# Decoder4_2.net
KiCad netlist of a schematic drawn in EAGLE
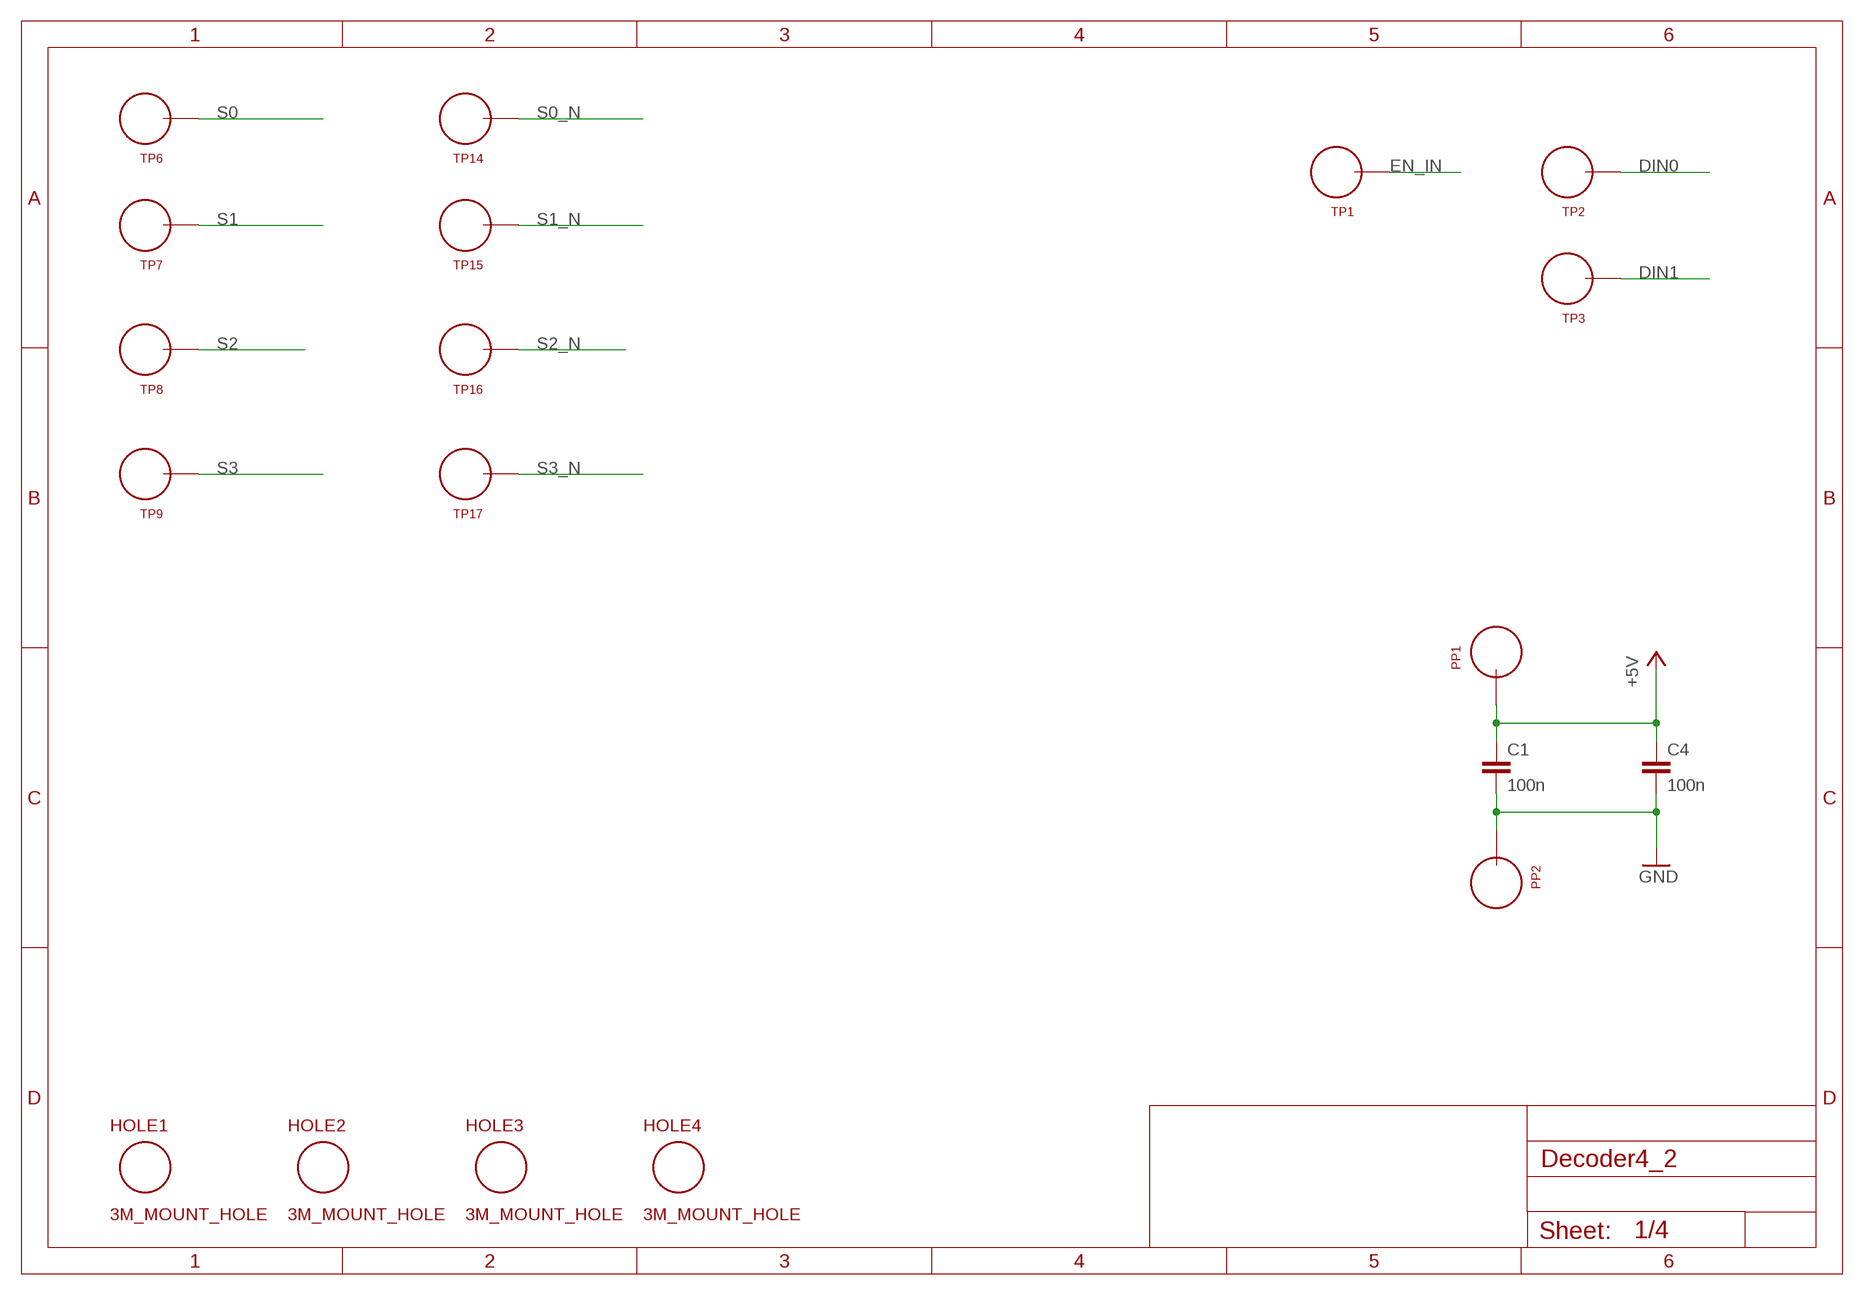
[diagram p0: schematic, sheet 1]
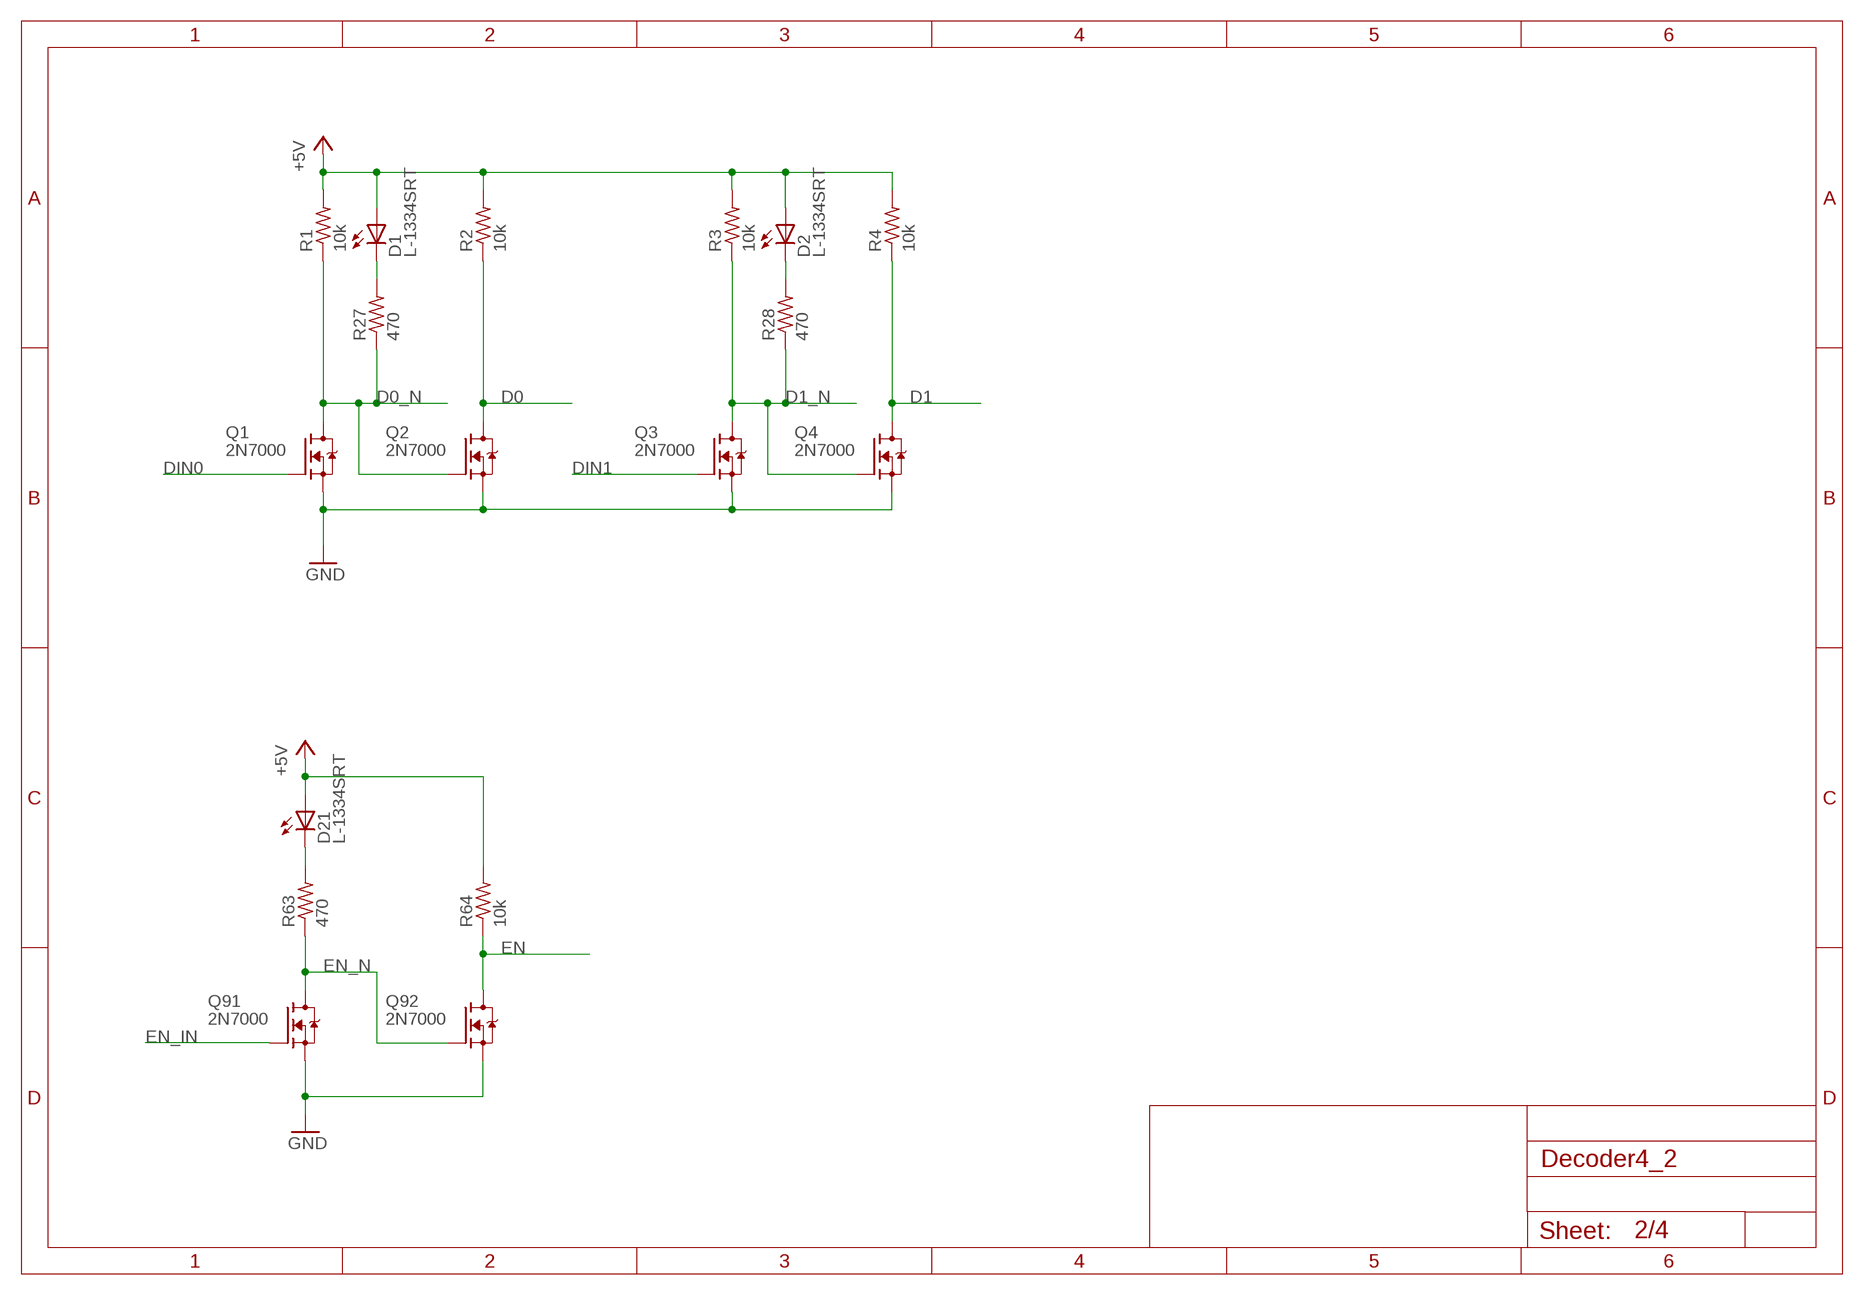
[diagram p1: schematic, sheet 2]
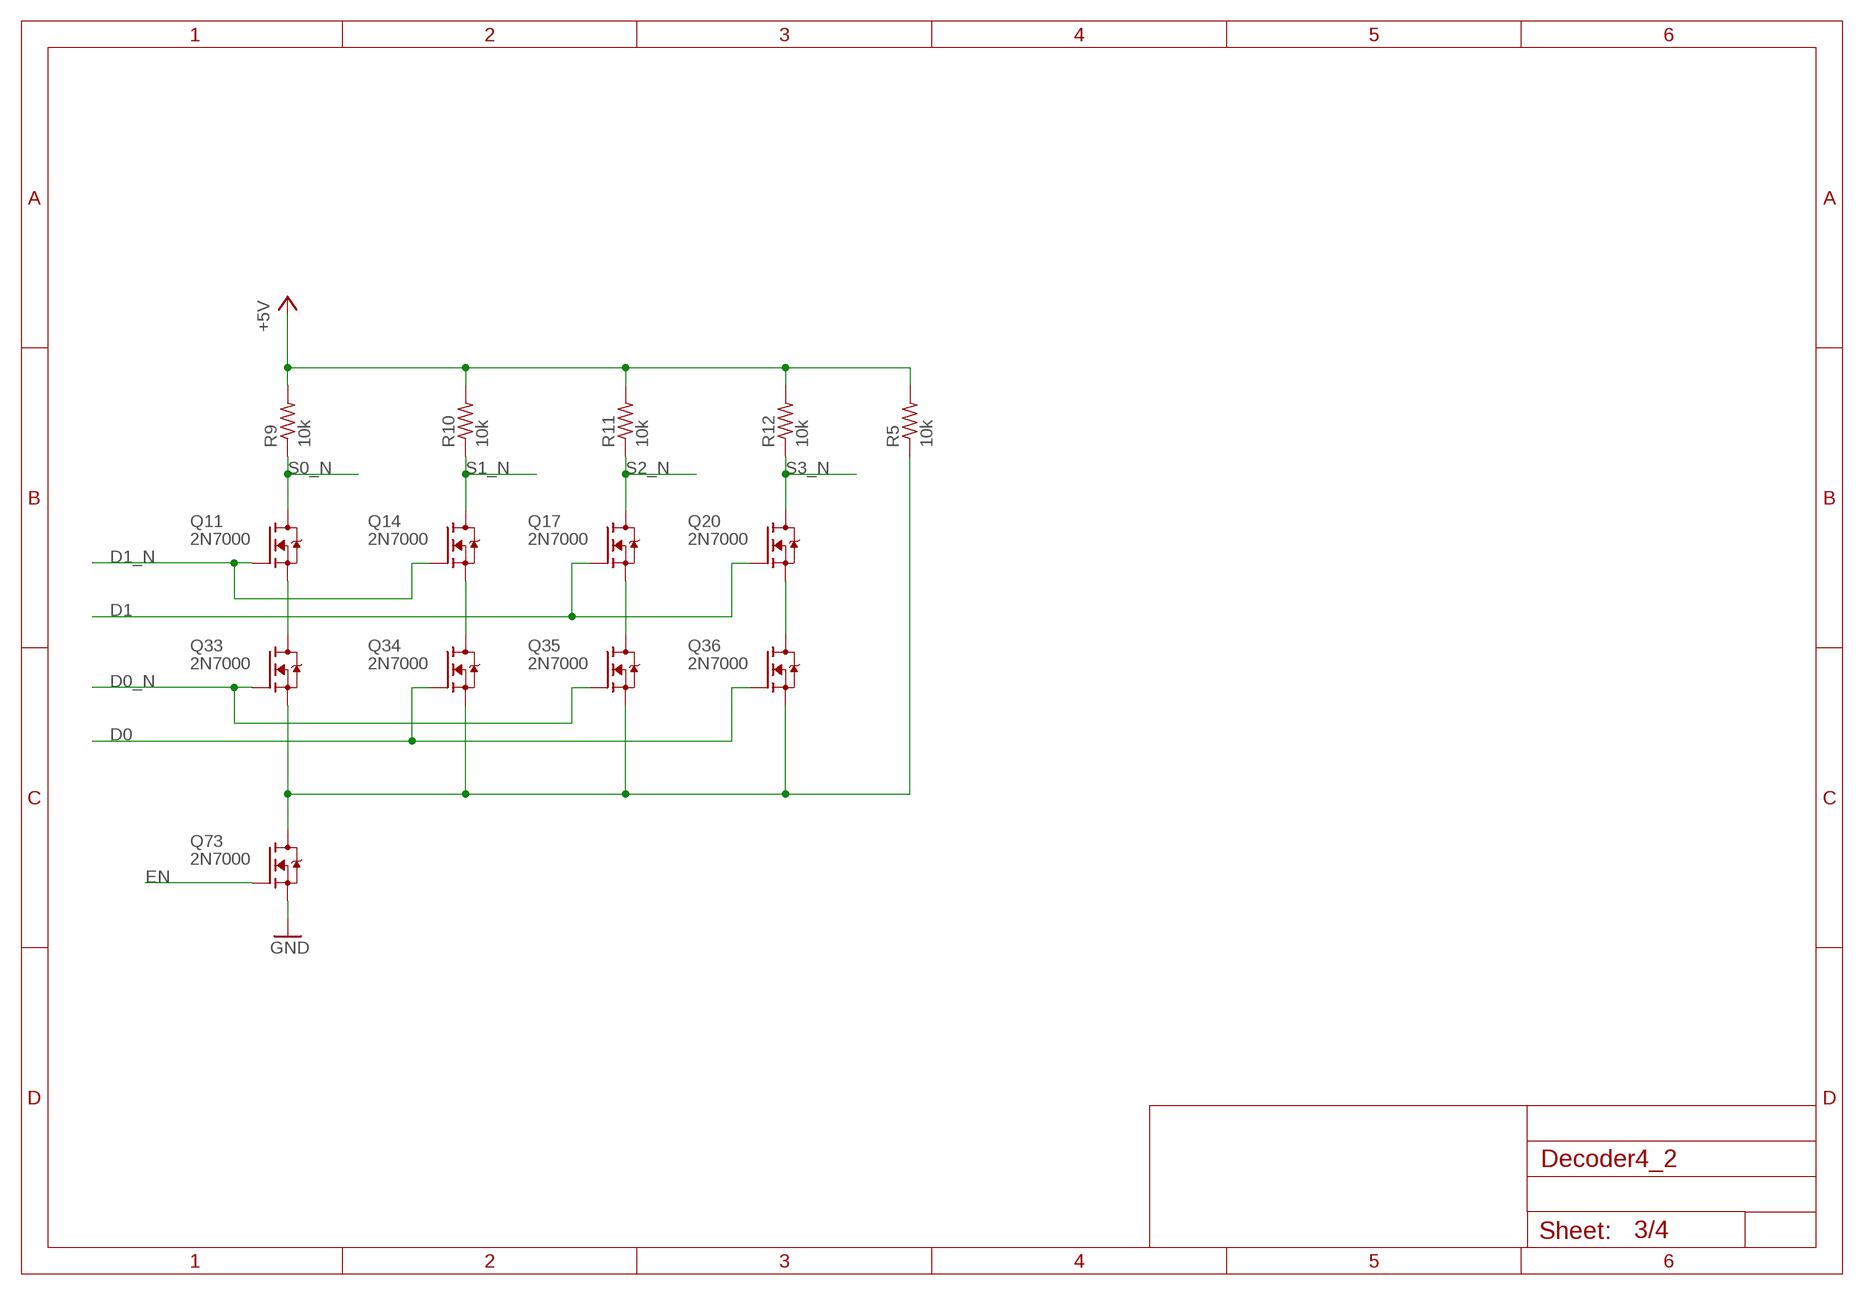
[diagram p2: schematic, sheet 3]
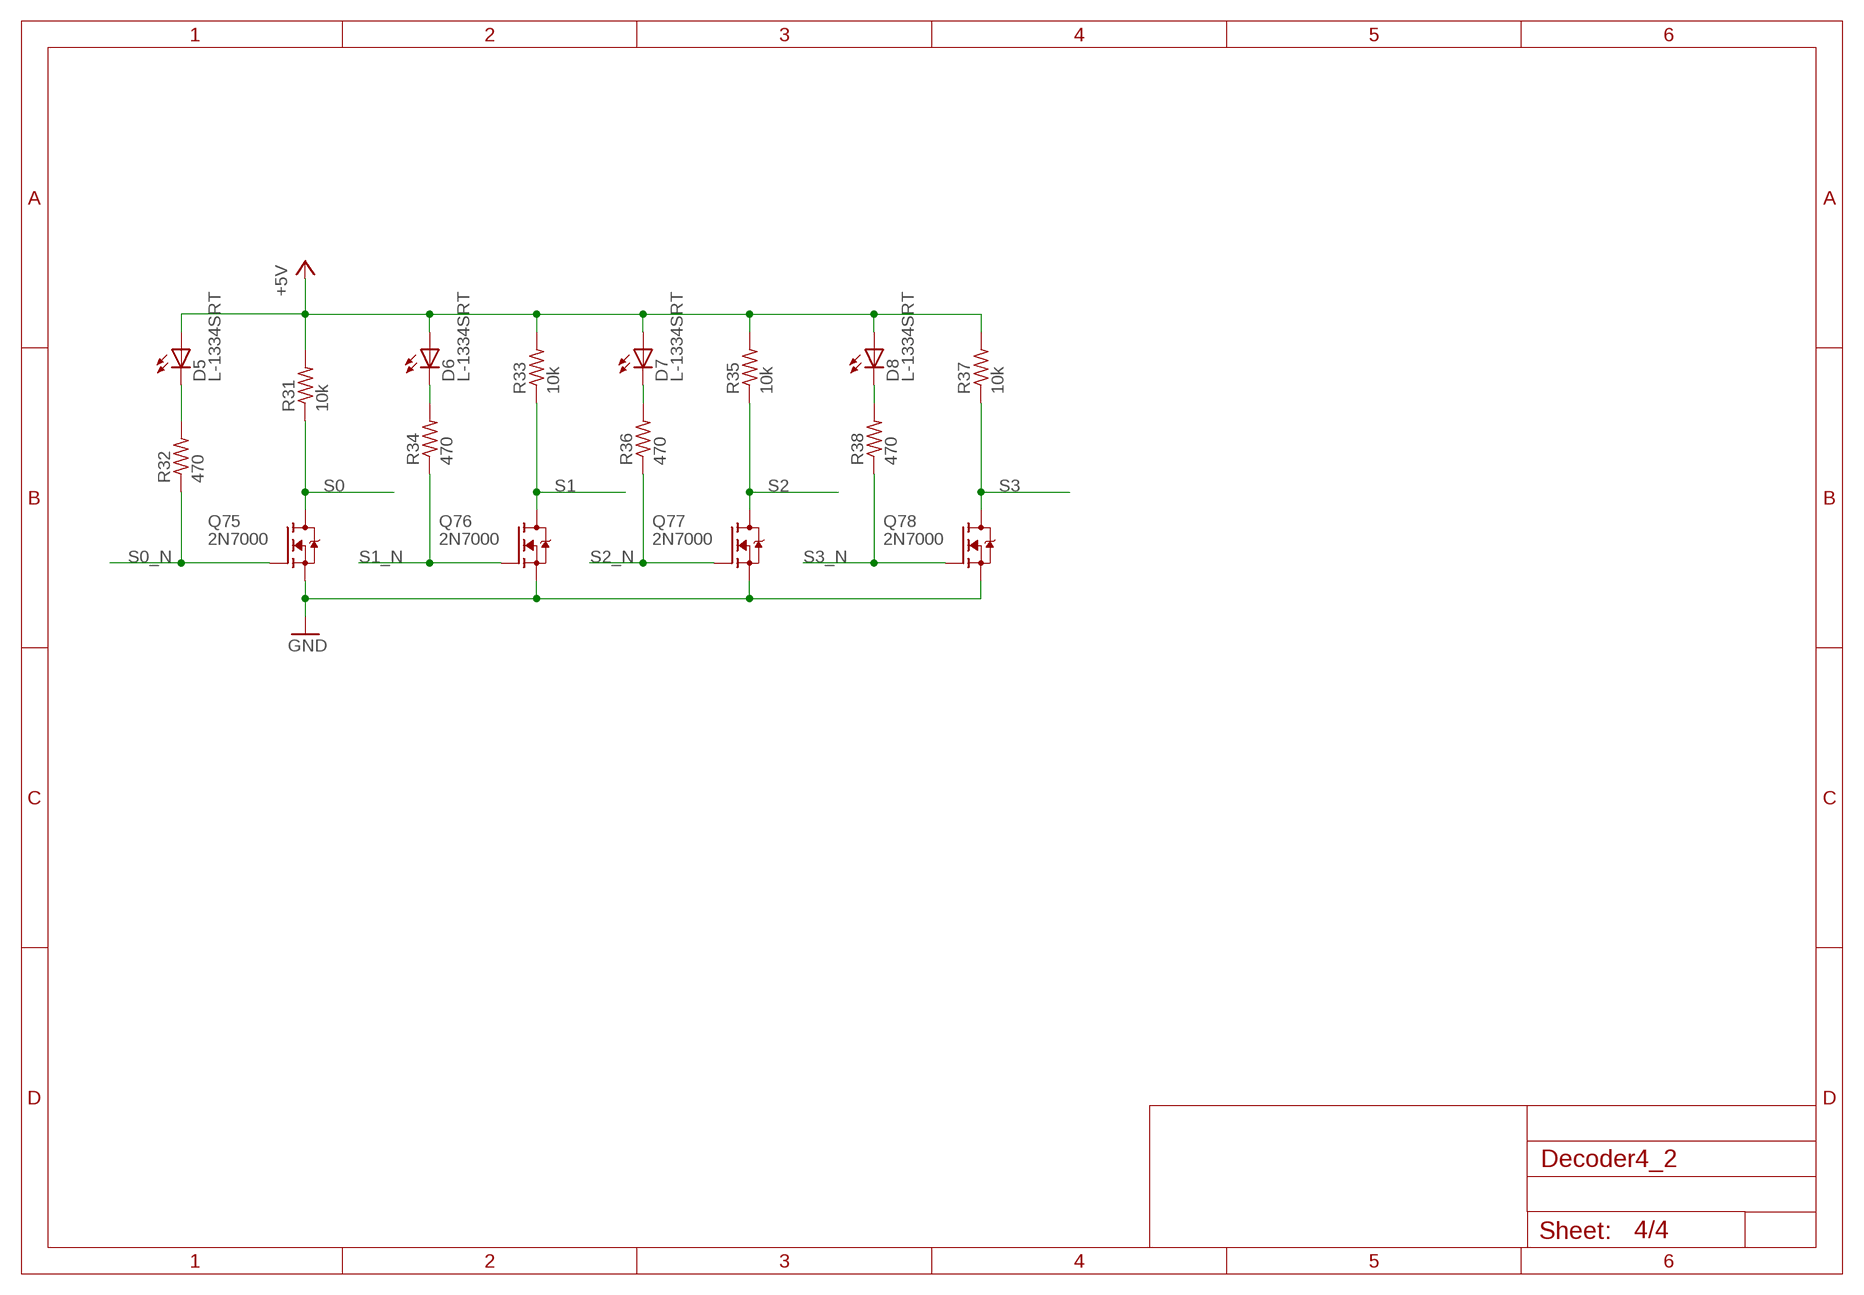
[diagram p3: schematic, sheet 4]

(export (version "E")
  (design (tool "Eeschema 10.0.6"))
  (components
    (comp (ref "D5")
      (value "L-1334SRT")
      (footprint "eagle-import:LED3MM")
      (libsource (lib "eagle-import") (part "L-1334SRT"))
    )
    (comp (ref "D6")
      (value "L-1334SRT")
      (footprint "eagle-import:LED3MM")
      (libsource (lib "eagle-import") (part "L-1334SRT"))
    )
    (comp (ref "D7")
      (value "L-1334SRT")
      (footprint "eagle-import:LED3MM")
      (libsource (lib "eagle-import") (part "L-1334SRT"))
    )
    (comp (ref "D8")
      (value "L-1334SRT")
      (footprint "eagle-import:LED3MM")
      (libsource (lib "eagle-import") (part "L-1334SRT"))
    )
    (comp (ref "Q75")
      (value "2N7000")
      (footprint "eagle-import:TO92-DGS")
      (libsource (lib "eagle-import") (part "2N7000"))
    )
    (comp (ref "Q76")
      (value "2N7000")
      (footprint "eagle-import:TO92-DGS")
      (libsource (lib "eagle-import") (part "2N7000"))
    )
    (comp (ref "Q77")
      (value "2N7000")
      (footprint "eagle-import:TO92-DGS")
      (libsource (lib "eagle-import") (part "2N7000"))
    )
    (comp (ref "Q78")
      (value "2N7000")
      (footprint "eagle-import:TO92-DGS")
      (libsource (lib "eagle-import") (part "2N7000"))
    )
    (comp (ref "R31")
      (value "10k")
      (footprint "eagle-import:R_P2INCH")
      (libsource (lib "eagle-import") (part "R_P2INCH"))
    )
    (comp (ref "R32")
      (value "470")
      (footprint "eagle-import:R_P2INCH")
      (libsource (lib "eagle-import") (part "R_P2INCH"))
    )
    (comp (ref "R33")
      (value "10k")
      (footprint "eagle-import:R_P2INCH")
      (libsource (lib "eagle-import") (part "R_P2INCH"))
    )
    (comp (ref "R34")
      (value "470")
      (footprint "eagle-import:R_P2INCH")
      (libsource (lib "eagle-import") (part "R_P2INCH"))
    )
    (comp (ref "R35")
      (value "10k")
      (footprint "eagle-import:R_P2INCH")
      (libsource (lib "eagle-import") (part "R_P2INCH"))
    )
    (comp (ref "R36")
      (value "470")
      (footprint "eagle-import:R_P2INCH")
      (libsource (lib "eagle-import") (part "R_P2INCH"))
    )
    (comp (ref "R37")
      (value "10k")
      (footprint "eagle-import:R_P2INCH")
      (libsource (lib "eagle-import") (part "R_P2INCH"))
    )
    (comp (ref "R38")
      (value "470")
      (footprint "eagle-import:R_P2INCH")
      (libsource (lib "eagle-import") (part "R_P2INCH"))
    )
    (comp (ref "Q11")
      (value "2N7000")
      (footprint "eagle-import:TO92-DGS")
      (libsource (lib "eagle-import") (part "2N7000"))
    )
    (comp (ref "Q14")
      (value "2N7000")
      (footprint "eagle-import:TO92-DGS")
      (libsource (lib "eagle-import") (part "2N7000"))
    )
    (comp (ref "Q17")
      (value "2N7000")
      (footprint "eagle-import:TO92-DGS")
      (libsource (lib "eagle-import") (part "2N7000"))
    )
    (comp (ref "Q20")
      (value "2N7000")
      (footprint "eagle-import:TO92-DGS")
      (libsource (lib "eagle-import") (part "2N7000"))
    )
    (comp (ref "Q33")
      (value "2N7000")
      (footprint "eagle-import:TO92-DGS")
      (libsource (lib "eagle-import") (part "2N7000"))
    )
    (comp (ref "Q34")
      (value "2N7000")
      (footprint "eagle-import:TO92-DGS")
      (libsource (lib "eagle-import") (part "2N7000"))
    )
    (comp (ref "Q35")
      (value "2N7000")
      (footprint "eagle-import:TO92-DGS")
      (libsource (lib "eagle-import") (part "2N7000"))
    )
    (comp (ref "Q36")
      (value "2N7000")
      (footprint "eagle-import:TO92-DGS")
      (libsource (lib "eagle-import") (part "2N7000"))
    )
    (comp (ref "Q73")
      (value "2N7000")
      (footprint "eagle-import:TO92-DGS")
      (libsource (lib "eagle-import") (part "2N7000"))
    )
    (comp (ref "R5")
      (value "10k")
      (footprint "eagle-import:R_P2INCH")
      (libsource (lib "eagle-import") (part "R_P2INCH"))
    )
    (comp (ref "R9")
      (value "10k")
      (footprint "eagle-import:R_P2INCH")
      (libsource (lib "eagle-import") (part "R_P2INCH"))
    )
    (comp (ref "R10")
      (value "10k")
      (footprint "eagle-import:R_P2INCH")
      (libsource (lib "eagle-import") (part "R_P2INCH"))
    )
    (comp (ref "R11")
      (value "10k")
      (footprint "eagle-import:R_P2INCH")
      (libsource (lib "eagle-import") (part "R_P2INCH"))
    )
    (comp (ref "R12")
      (value "10k")
      (footprint "eagle-import:R_P2INCH")
      (libsource (lib "eagle-import") (part "R_P2INCH"))
    )
    (comp (ref "C1")
      (value "100n")
      (footprint "eagle-import:CAP_P2INCH")
      (libsource (lib "eagle-import") (part "C_P2INCH"))
    )
    (comp (ref "C4")
      (value "100n")
      (footprint "eagle-import:CAP_P2INCH")
      (libsource (lib "eagle-import") (part "C_P2INCH"))
    )
    (comp (ref "HOLE1")
      (value "3M_MOUNT_HOLE")
      (footprint "eagle-import:3M_HOLE")
      (libsource (lib "eagle-import") (part "3M_MOUNT_HOLE"))
    )
    (comp (ref "HOLE2")
      (value "3M_MOUNT_HOLE")
      (footprint "eagle-import:3M_HOLE")
      (libsource (lib "eagle-import") (part "3M_MOUNT_HOLE"))
    )
    (comp (ref "HOLE3")
      (value "3M_MOUNT_HOLE")
      (footprint "eagle-import:3M_HOLE")
      (libsource (lib "eagle-import") (part "3M_MOUNT_HOLE"))
    )
    (comp (ref "HOLE4")
      (value "3M_MOUNT_HOLE")
      (footprint "eagle-import:3M_HOLE")
      (libsource (lib "eagle-import") (part "3M_MOUNT_HOLE"))
    )
    (comp (ref "PP1")
      (value "TEST_LOOP")
      (footprint "eagle-import:TEST_LOOP")
      (libsource (lib "eagle-import") (part "TEST_LOOP"))
    )
    (comp (ref "PP2")
      (value "TEST_LOOP")
      (footprint "eagle-import:TEST_LOOP")
      (libsource (lib "eagle-import") (part "TEST_LOOP"))
    )
    (comp (ref "TP1")
      (value "TEST_LOOP")
      (footprint "eagle-import:TEST_LOOP")
      (libsource (lib "eagle-import") (part "TEST_LOOP"))
    )
    (comp (ref "TP2")
      (value "TEST_LOOP")
      (footprint "eagle-import:TEST_LOOP")
      (libsource (lib "eagle-import") (part "TEST_LOOP"))
    )
    (comp (ref "TP3")
      (value "TEST_LOOP")
      (footprint "eagle-import:TEST_LOOP")
      (libsource (lib "eagle-import") (part "TEST_LOOP"))
    )
    (comp (ref "TP6")
      (value "TEST_LOOP")
      (footprint "eagle-import:TEST_LOOP")
      (libsource (lib "eagle-import") (part "TEST_LOOP"))
    )
    (comp (ref "TP7")
      (value "TEST_LOOP")
      (footprint "eagle-import:TEST_LOOP")
      (libsource (lib "eagle-import") (part "TEST_LOOP"))
    )
    (comp (ref "TP8")
      (value "TEST_LOOP")
      (footprint "eagle-import:TEST_LOOP")
      (libsource (lib "eagle-import") (part "TEST_LOOP"))
    )
    (comp (ref "TP9")
      (value "TEST_LOOP")
      (footprint "eagle-import:TEST_LOOP")
      (libsource (lib "eagle-import") (part "TEST_LOOP"))
    )
    (comp (ref "TP14")
      (value "TEST_LOOP")
      (footprint "eagle-import:TEST_LOOP")
      (libsource (lib "eagle-import") (part "TEST_LOOP"))
    )
    (comp (ref "TP15")
      (value "TEST_LOOP")
      (footprint "eagle-import:TEST_LOOP")
      (libsource (lib "eagle-import") (part "TEST_LOOP"))
    )
    (comp (ref "TP16")
      (value "TEST_LOOP")
      (footprint "eagle-import:TEST_LOOP")
      (libsource (lib "eagle-import") (part "TEST_LOOP"))
    )
    (comp (ref "TP17")
      (value "TEST_LOOP")
      (footprint "eagle-import:TEST_LOOP")
      (libsource (lib "eagle-import") (part "TEST_LOOP"))
    )
    (comp (ref "D1")
      (value "L-1334SRT")
      (footprint "eagle-import:LED3MM")
      (libsource (lib "eagle-import") (part "L-1334SRT"))
    )
    (comp (ref "D2")
      (value "L-1334SRT")
      (footprint "eagle-import:LED3MM")
      (libsource (lib "eagle-import") (part "L-1334SRT"))
    )
    (comp (ref "D21")
      (value "L-1334SRT")
      (footprint "eagle-import:LED3MM")
      (libsource (lib "eagle-import") (part "L-1334SRT"))
    )
    (comp (ref "Q1")
      (value "2N7000")
      (footprint "eagle-import:TO92-DGS")
      (libsource (lib "eagle-import") (part "2N7000"))
    )
    (comp (ref "Q2")
      (value "2N7000")
      (footprint "eagle-import:TO92-DGS")
      (libsource (lib "eagle-import") (part "2N7000"))
    )
    (comp (ref "Q3")
      (value "2N7000")
      (footprint "eagle-import:TO92-DGS")
      (libsource (lib "eagle-import") (part "2N7000"))
    )
    (comp (ref "Q4")
      (value "2N7000")
      (footprint "eagle-import:TO92-DGS")
      (libsource (lib "eagle-import") (part "2N7000"))
    )
    (comp (ref "Q91")
      (value "2N7000")
      (footprint "eagle-import:TO92-DGS")
      (libsource (lib "eagle-import") (part "2N7000"))
    )
    (comp (ref "Q92")
      (value "2N7000")
      (footprint "eagle-import:TO92-DGS")
      (libsource (lib "eagle-import") (part "2N7000"))
    )
    (comp (ref "R1")
      (value "10k")
      (footprint "eagle-import:R_P2INCH")
      (libsource (lib "eagle-import") (part "R_P2INCH"))
    )
    (comp (ref "R2")
      (value "10k")
      (footprint "eagle-import:R_P2INCH")
      (libsource (lib "eagle-import") (part "R_P2INCH"))
    )
    (comp (ref "R3")
      (value "10k")
      (footprint "eagle-import:R_P2INCH")
      (libsource (lib "eagle-import") (part "R_P2INCH"))
    )
    (comp (ref "R4")
      (value "10k")
      (footprint "eagle-import:R_P2INCH")
      (libsource (lib "eagle-import") (part "R_P2INCH"))
    )
    (comp (ref "R27")
      (value "470")
      (footprint "eagle-import:R_P2INCH")
      (libsource (lib "eagle-import") (part "R_P2INCH"))
    )
    (comp (ref "R28")
      (value "470")
      (footprint "eagle-import:R_P2INCH")
      (libsource (lib "eagle-import") (part "R_P2INCH"))
    )
    (comp (ref "R63")
      (value "470")
      (footprint "eagle-import:R_P2INCH")
      (libsource (lib "eagle-import") (part "R_P2INCH"))
    )
    (comp (ref "R64")
      (value "10k")
      (footprint "eagle-import:R_P2INCH")
      (libsource (lib "eagle-import") (part "R_P2INCH"))
    )
  )
  (nets
    (net (code "1") (name "+5V") (class "Default")
      (node (ref "C1") (pin "1") (pinfunction "1_1") (pintype "passive"))
      (node (ref "C4") (pin "1") (pinfunction "1_1") (pintype "passive"))
      (node (ref "D1") (pin "A") (pinfunction "A_A") (pintype "passive"))
      (node (ref "D2") (pin "A") (pinfunction "A_A") (pintype "passive"))
      (node (ref "D21") (pin "A") (pinfunction "A_A") (pintype "passive"))
      (node (ref "D5") (pin "A") (pinfunction "A_A") (pintype "passive"))
      (node (ref "D6") (pin "A") (pinfunction "A_A") (pintype "passive"))
      (node (ref "D7") (pin "A") (pinfunction "A_A") (pintype "passive"))
      (node (ref "D8") (pin "A") (pinfunction "A_A") (pintype "passive"))
      (node (ref "PP1") (pin "P$1") (pinfunction "P$1_P$1") (pintype "bidirectional"))
      (node (ref "R1") (pin "2") (pinfunction "2_2") (pintype "passive"))
      (node (ref "R10") (pin "2") (pinfunction "2_2") (pintype "passive"))
      (node (ref "R11") (pin "2") (pinfunction "2_2") (pintype "passive"))
      (node (ref "R12") (pin "2") (pinfunction "2_2") (pintype "passive"))
      (node (ref "R2") (pin "2") (pinfunction "2_2") (pintype "passive"))
      (node (ref "R3") (pin "2") (pinfunction "2_2") (pintype "passive"))
      (node (ref "R31") (pin "2") (pinfunction "2_2") (pintype "passive"))
      (node (ref "R33") (pin "2") (pinfunction "2_2") (pintype "passive"))
      (node (ref "R35") (pin "2") (pinfunction "2_2") (pintype "passive"))
      (node (ref "R37") (pin "2") (pinfunction "2_2") (pintype "passive"))
      (node (ref "R4") (pin "2") (pinfunction "2_2") (pintype "passive"))
      (node (ref "R5") (pin "2") (pinfunction "2_2") (pintype "passive"))
      (node (ref "R64") (pin "2") (pinfunction "2_2") (pintype "passive"))
      (node (ref "R9") (pin "2") (pinfunction "2_2") (pintype "passive"))
    )
    (net (code "2") (name "D0") (class "Default")
      (node (ref "Q2") (pin "D") (pinfunction "D_D") (pintype "passive"))
      (node (ref "Q34") (pin "G") (pinfunction "G_G") (pintype "passive"))
      (node (ref "Q36") (pin "G") (pinfunction "G_G") (pintype "passive"))
      (node (ref "R2") (pin "1") (pinfunction "1_1") (pintype "passive"))
    )
    (net (code "3") (name "D0_N") (class "Default")
      (node (ref "Q1") (pin "D") (pinfunction "D_D") (pintype "passive"))
      (node (ref "Q2") (pin "G") (pinfunction "G_G") (pintype "passive"))
      (node (ref "Q33") (pin "G") (pinfunction "G_G") (pintype "passive"))
      (node (ref "Q35") (pin "G") (pinfunction "G_G") (pintype "passive"))
      (node (ref "R1") (pin "1") (pinfunction "1_1") (pintype "passive"))
      (node (ref "R27") (pin "1") (pinfunction "1_1") (pintype "passive"))
    )
    (net (code "4") (name "D1") (class "Default")
      (node (ref "Q17") (pin "G") (pinfunction "G_G") (pintype "passive"))
      (node (ref "Q20") (pin "G") (pinfunction "G_G") (pintype "passive"))
      (node (ref "Q4") (pin "D") (pinfunction "D_D") (pintype "passive"))
      (node (ref "R4") (pin "1") (pinfunction "1_1") (pintype "passive"))
    )
    (net (code "5") (name "D1_N") (class "Default")
      (node (ref "Q11") (pin "G") (pinfunction "G_G") (pintype "passive"))
      (node (ref "Q14") (pin "G") (pinfunction "G_G") (pintype "passive"))
      (node (ref "Q3") (pin "D") (pinfunction "D_D") (pintype "passive"))
      (node (ref "Q4") (pin "G") (pinfunction "G_G") (pintype "passive"))
      (node (ref "R28") (pin "1") (pinfunction "1_1") (pintype "passive"))
      (node (ref "R3") (pin "1") (pinfunction "1_1") (pintype "passive"))
    )
    (net (code "6") (name "DIN0") (class "Default")
      (node (ref "Q1") (pin "G") (pinfunction "G_G") (pintype "passive"))
      (node (ref "TP2") (pin "P$1") (pinfunction "P$1_P$1") (pintype "bidirectional"))
    )
    (net (code "7") (name "DIN1") (class "Default")
      (node (ref "Q3") (pin "G") (pinfunction "G_G") (pintype "passive"))
      (node (ref "TP3") (pin "P$1") (pinfunction "P$1_P$1") (pintype "bidirectional"))
    )
    (net (code "8") (name "EN") (class "Default")
      (node (ref "Q73") (pin "G") (pinfunction "G_G") (pintype "passive"))
      (node (ref "Q92") (pin "D") (pinfunction "D_D") (pintype "passive"))
      (node (ref "R64") (pin "1") (pinfunction "1_1") (pintype "passive"))
    )
    (net (code "9") (name "EN_IN") (class "Default")
      (node (ref "Q91") (pin "G") (pinfunction "G_G") (pintype "passive"))
      (node (ref "TP1") (pin "P$1") (pinfunction "P$1_P$1") (pintype "bidirectional"))
    )
    (net (code "10") (name "EN_N") (class "Default")
      (node (ref "Q91") (pin "D") (pinfunction "D_D") (pintype "passive"))
      (node (ref "Q92") (pin "G") (pinfunction "G_G") (pintype "passive"))
      (node (ref "R63") (pin "1") (pinfunction "1_1") (pintype "passive"))
    )
    (net (code "11") (name "GND") (class "Default")
      (node (ref "C1") (pin "2") (pinfunction "2_2") (pintype "passive"))
      (node (ref "C4") (pin "2") (pinfunction "2_2") (pintype "passive"))
      (node (ref "PP2") (pin "P$1") (pinfunction "P$1_P$1") (pintype "bidirectional"))
      (node (ref "Q1") (pin "S") (pinfunction "S_S") (pintype "passive"))
      (node (ref "Q2") (pin "S") (pinfunction "S_S") (pintype "passive"))
      (node (ref "Q3") (pin "S") (pinfunction "S_S") (pintype "passive"))
      (node (ref "Q4") (pin "S") (pinfunction "S_S") (pintype "passive"))
      (node (ref "Q73") (pin "S") (pinfunction "S_S") (pintype "passive"))
      (node (ref "Q75") (pin "S") (pinfunction "S_S") (pintype "passive"))
      (node (ref "Q76") (pin "S") (pinfunction "S_S") (pintype "passive"))
      (node (ref "Q77") (pin "S") (pinfunction "S_S") (pintype "passive"))
      (node (ref "Q78") (pin "S") (pinfunction "S_S") (pintype "passive"))
      (node (ref "Q91") (pin "S") (pinfunction "S_S") (pintype "passive"))
      (node (ref "Q92") (pin "S") (pinfunction "S_S") (pintype "passive"))
    )
    (net (code "12") (name "Net-(D1-C)") (class "Default")
      (node (ref "D1") (pin "K") (pinfunction "C_K") (pintype "passive"))
      (node (ref "R27") (pin "2") (pinfunction "2_2") (pintype "passive"))
    )
    (net (code "13") (name "Net-(D2-C)") (class "Default")
      (node (ref "D2") (pin "K") (pinfunction "C_K") (pintype "passive"))
      (node (ref "R28") (pin "2") (pinfunction "2_2") (pintype "passive"))
    )
    (net (code "14") (name "Net-(D5-C)") (class "Default")
      (node (ref "D5") (pin "K") (pinfunction "C_K") (pintype "passive"))
      (node (ref "R32") (pin "2") (pinfunction "2_2") (pintype "passive"))
    )
    (net (code "15") (name "Net-(D6-C)") (class "Default")
      (node (ref "D6") (pin "K") (pinfunction "C_K") (pintype "passive"))
      (node (ref "R34") (pin "2") (pinfunction "2_2") (pintype "passive"))
    )
    (net (code "16") (name "Net-(D7-C)") (class "Default")
      (node (ref "D7") (pin "K") (pinfunction "C_K") (pintype "passive"))
      (node (ref "R36") (pin "2") (pinfunction "2_2") (pintype "passive"))
    )
    (net (code "17") (name "Net-(D8-C)") (class "Default")
      (node (ref "D8") (pin "K") (pinfunction "C_K") (pintype "passive"))
      (node (ref "R38") (pin "2") (pinfunction "2_2") (pintype "passive"))
    )
    (net (code "18") (name "Net-(D21-C)") (class "Default")
      (node (ref "D21") (pin "K") (pinfunction "C_K") (pintype "passive"))
      (node (ref "R63") (pin "2") (pinfunction "2_2") (pintype "passive"))
    )
    (net (code "19") (name "Net-(Q11-PadS)") (class "Default")
      (node (ref "Q11") (pin "S") (pinfunction "S_S") (pintype "passive"))
      (node (ref "Q33") (pin "D") (pinfunction "D_D") (pintype "passive"))
    )
    (net (code "20") (name "Net-(Q14-PadS)") (class "Default")
      (node (ref "Q14") (pin "S") (pinfunction "S_S") (pintype "passive"))
      (node (ref "Q34") (pin "D") (pinfunction "D_D") (pintype "passive"))
    )
    (net (code "21") (name "Net-(Q17-PadS)") (class "Default")
      (node (ref "Q17") (pin "S") (pinfunction "S_S") (pintype "passive"))
      (node (ref "Q35") (pin "D") (pinfunction "D_D") (pintype "passive"))
    )
    (net (code "22") (name "Net-(Q20-PadS)") (class "Default")
      (node (ref "Q20") (pin "S") (pinfunction "S_S") (pintype "passive"))
      (node (ref "Q36") (pin "D") (pinfunction "D_D") (pintype "passive"))
    )
    (net (code "23") (name "Net-(Q33-PadS)") (class "Default")
      (node (ref "Q33") (pin "S") (pinfunction "S_S") (pintype "passive"))
      (node (ref "Q34") (pin "S") (pinfunction "S_S") (pintype "passive"))
      (node (ref "Q35") (pin "S") (pinfunction "S_S") (pintype "passive"))
      (node (ref "Q36") (pin "S") (pinfunction "S_S") (pintype "passive"))
      (node (ref "Q73") (pin "D") (pinfunction "D_D") (pintype "passive"))
      (node (ref "R5") (pin "1") (pinfunction "1_1") (pintype "passive"))
    )
    (net (code "24") (name "S0") (class "Default")
      (node (ref "Q75") (pin "D") (pinfunction "D_D") (pintype "passive"))
      (node (ref "R31") (pin "1") (pinfunction "1_1") (pintype "passive"))
      (node (ref "TP6") (pin "P$1") (pinfunction "P$1_P$1") (pintype "bidirectional"))
    )
    (net (code "25") (name "S0_N") (class "Default")
      (node (ref "Q11") (pin "D") (pinfunction "D_D") (pintype "passive"))
      (node (ref "Q75") (pin "G") (pinfunction "G_G") (pintype "passive"))
      (node (ref "R32") (pin "1") (pinfunction "1_1") (pintype "passive"))
      (node (ref "R9") (pin "1") (pinfunction "1_1") (pintype "passive"))
      (node (ref "TP14") (pin "P$1") (pinfunction "P$1_P$1") (pintype "bidirectional"))
    )
    (net (code "26") (name "S1") (class "Default")
      (node (ref "Q76") (pin "D") (pinfunction "D_D") (pintype "passive"))
      (node (ref "R33") (pin "1") (pinfunction "1_1") (pintype "passive"))
      (node (ref "TP7") (pin "P$1") (pinfunction "P$1_P$1") (pintype "bidirectional"))
    )
    (net (code "27") (name "S1_N") (class "Default")
      (node (ref "Q14") (pin "D") (pinfunction "D_D") (pintype "passive"))
      (node (ref "Q76") (pin "G") (pinfunction "G_G") (pintype "passive"))
      (node (ref "R10") (pin "1") (pinfunction "1_1") (pintype "passive"))
      (node (ref "R34") (pin "1") (pinfunction "1_1") (pintype "passive"))
      (node (ref "TP15") (pin "P$1") (pinfunction "P$1_P$1") (pintype "bidirectional"))
    )
    (net (code "28") (name "S2") (class "Default")
      (node (ref "Q77") (pin "D") (pinfunction "D_D") (pintype "passive"))
      (node (ref "R35") (pin "1") (pinfunction "1_1") (pintype "passive"))
      (node (ref "TP8") (pin "P$1") (pinfunction "P$1_P$1") (pintype "bidirectional"))
    )
    (net (code "29") (name "S2_N") (class "Default")
      (node (ref "Q17") (pin "D") (pinfunction "D_D") (pintype "passive"))
      (node (ref "Q77") (pin "G") (pinfunction "G_G") (pintype "passive"))
      (node (ref "R11") (pin "1") (pinfunction "1_1") (pintype "passive"))
      (node (ref "R36") (pin "1") (pinfunction "1_1") (pintype "passive"))
      (node (ref "TP16") (pin "P$1") (pinfunction "P$1_P$1") (pintype "bidirectional"))
    )
    (net (code "30") (name "S3") (class "Default")
      (node (ref "Q78") (pin "D") (pinfunction "D_D") (pintype "passive"))
      (node (ref "R37") (pin "1") (pinfunction "1_1") (pintype "passive"))
      (node (ref "TP9") (pin "P$1") (pinfunction "P$1_P$1") (pintype "bidirectional"))
    )
    (net (code "31") (name "S3_N") (class "Default")
      (node (ref "Q20") (pin "D") (pinfunction "D_D") (pintype "passive"))
      (node (ref "Q78") (pin "G") (pinfunction "G_G") (pintype "passive"))
      (node (ref "R12") (pin "1") (pinfunction "1_1") (pintype "passive"))
      (node (ref "R38") (pin "1") (pinfunction "1_1") (pintype "passive"))
      (node (ref "TP17") (pin "P$1") (pinfunction "P$1_P$1") (pintype "bidirectional"))
    )
  )
)
